# twomics_sw_led_v2.net
KiCad netlist of a schematic drawn in EAGLE
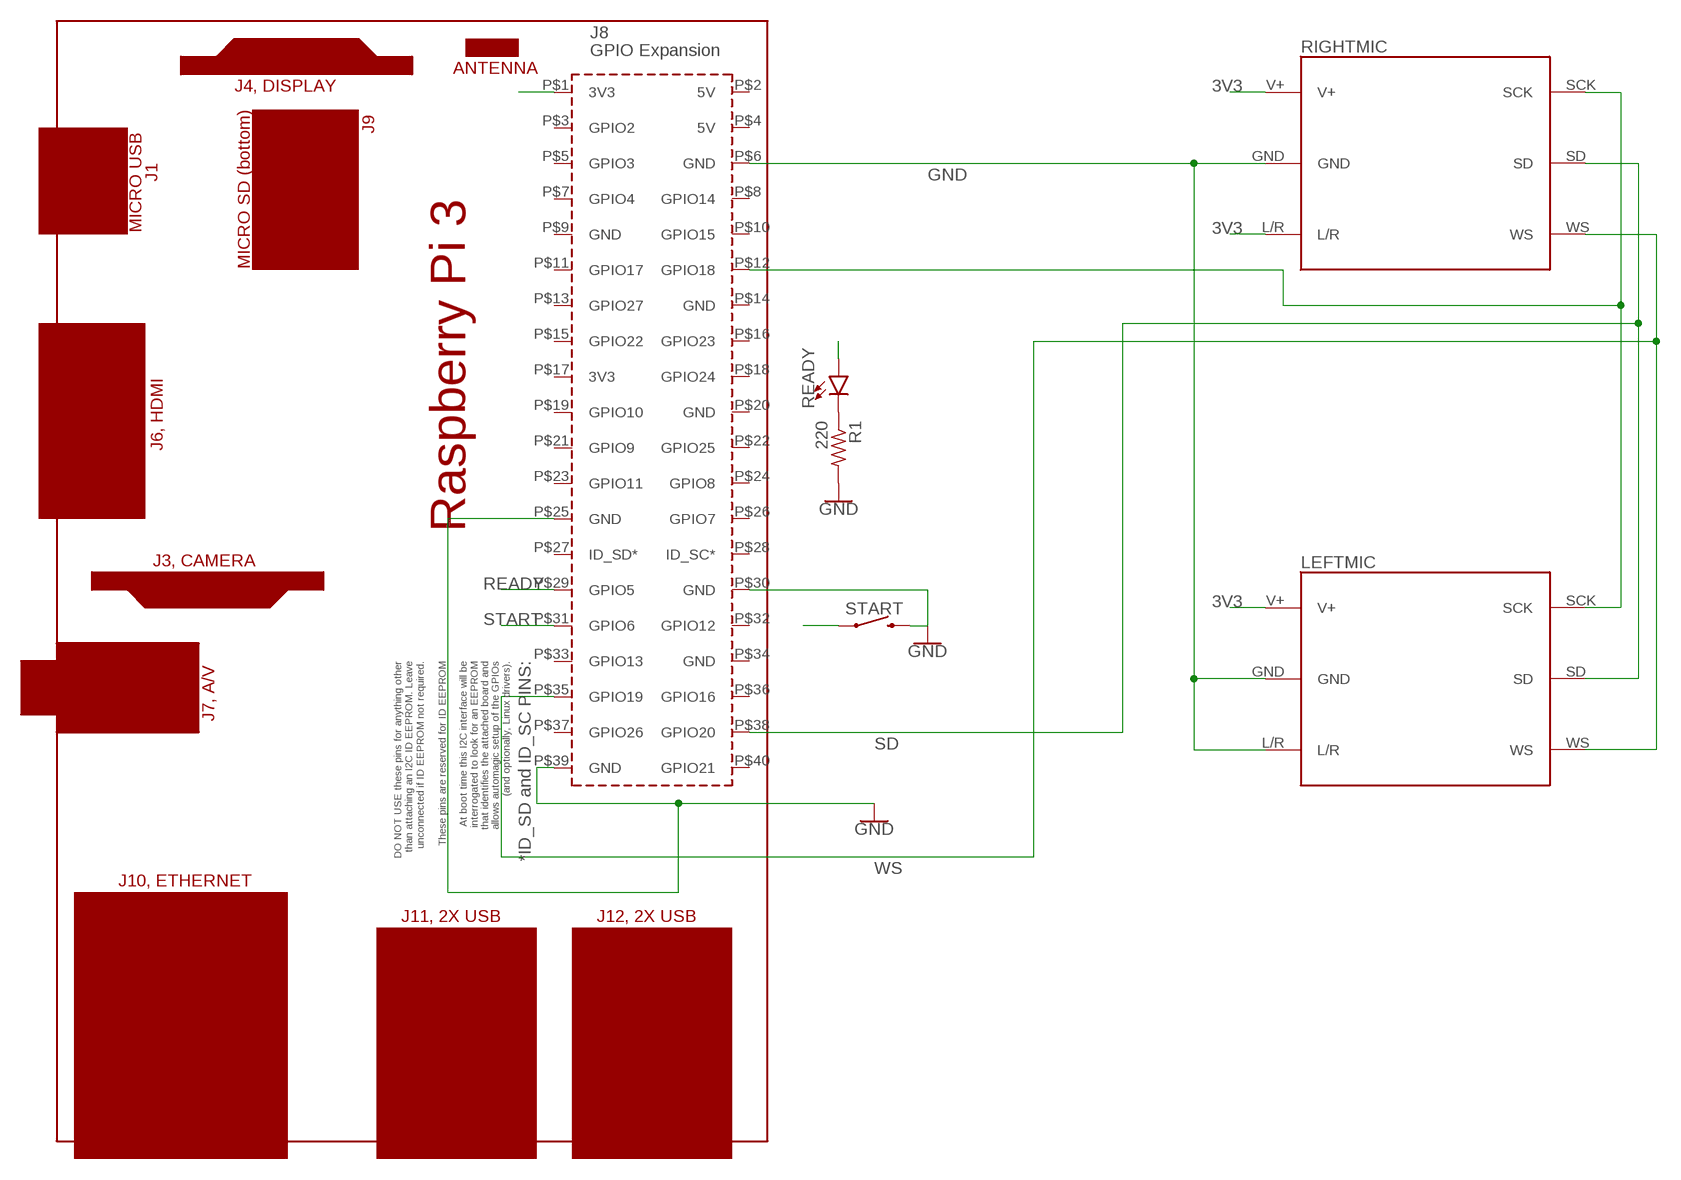
[diagram p0: schematic, sheet 1]

(export (version "E")
  (design (tool "Eeschema 10.0.6"))
  (components
    (comp (ref "LEFTMIC")
      (value "EMMIC-ICS43432")
      (footprint "eagle-import:PTH")
      (libsource (lib "eagle-import") (part "EMMIC-ICS43432"))
    )
    (comp (ref "PCB1")
      (value "RPI3_40_PIN")
      (footprint "eagle-import:40_PIN")
      (libsource (lib "eagle-import") (part "RPI3_40_PIN"))
    )
    (comp (ref "R1")
      (value "220")
      (footprint "eagle-import:0207_7")
      (libsource (lib "eagle-import") (part "R-US_0207/7"))
    )
    (comp (ref "READY")
      (value "LED3MM")
      (footprint "eagle-import:LED_3MM")
      (libsource (lib "eagle-import") (part "LED3MM"))
    )
    (comp (ref "RIGHTMIC")
      (value "EMMIC-ICS43432")
      (footprint "eagle-import:PTH")
      (libsource (lib "eagle-import") (part "EMMIC-ICS43432"))
    )
    (comp (ref "START")
      (value "MOMENTARY-SWITCH-SPST-PTH-6.0MM")
      (footprint "eagle-import:TACTILE_SWITCH_PTH_6.0MM")
      (libsource (lib "eagle-import") (part "MOMENTARY-SWITCH-SPST-PTH-6.0MM"))
    )
  )
  (nets
    (net (code "1") (name "/3V3") (class "Default")
      (node (ref "LEFTMIC") (pin "V+") (pinfunction "V+_V+") (pintype "bidirectional"))
      (node (ref "PCB1") (pin "P$1") (pinfunction "3V3_P$1") (pintype "bidirectional"))
      (node (ref "RIGHTMIC") (pin "L/R") (pinfunction "L/R_L/R") (pintype "bidirectional"))
      (node (ref "RIGHTMIC") (pin "V+") (pinfunction "V+_V+") (pintype "bidirectional"))
    )
    (net (code "2") (name "/READY") (class "Default")
      (node (ref "PCB1") (pin "P$29") (pinfunction "GPIO5_P$29") (pintype "bidirectional"))
      (node (ref "READY") (pin "A") (pinfunction "A_A") (pintype "passive"))
    )
    (net (code "3") (name "/SD") (class "Default")
      (node (ref "LEFTMIC") (pin "SD") (pinfunction "SD_SD") (pintype "bidirectional"))
      (node (ref "PCB1") (pin "P$38") (pinfunction "GPIO20_P$38") (pintype "bidirectional"))
      (node (ref "RIGHTMIC") (pin "SD") (pinfunction "SD_SD") (pintype "bidirectional"))
    )
    (net (code "4") (name "/START") (class "Default")
      (node (ref "PCB1") (pin "P$31") (pinfunction "GPIO6_P$31") (pintype "bidirectional"))
      (node (ref "START") (pin "1") (pinfunction "1_1") (pintype "passive"))
    )
    (net (code "5") (name "/WS") (class "Default")
      (node (ref "LEFTMIC") (pin "WS") (pinfunction "WS_WS") (pintype "bidirectional"))
      (node (ref "PCB1") (pin "P$35") (pinfunction "GPIO19_P$35") (pintype "bidirectional"))
      (node (ref "RIGHTMIC") (pin "WS") (pinfunction "WS_WS") (pintype "bidirectional"))
    )
    (net (code "6") (name "GND") (class "Default")
      (node (ref "LEFTMIC") (pin "GND") (pinfunction "GND_GND") (pintype "bidirectional"))
      (node (ref "LEFTMIC") (pin "L/R") (pinfunction "L/R_L/R") (pintype "bidirectional"))
      (node (ref "PCB1") (pin "P$25") (pinfunction "GND_P$25") (pintype "bidirectional"))
      (node (ref "PCB1") (pin "P$30") (pinfunction "GND_P$30") (pintype "bidirectional"))
      (node (ref "PCB1") (pin "P$39") (pinfunction "GND_P$39") (pintype "bidirectional"))
      (node (ref "PCB1") (pin "P$6") (pinfunction "GND_P$6") (pintype "bidirectional"))
      (node (ref "R1") (pin "2") (pinfunction "2_2") (pintype "passive"))
      (node (ref "RIGHTMIC") (pin "GND") (pinfunction "GND_GND") (pintype "bidirectional"))
      (node (ref "START") (pin "3") (pinfunction "2_3") (pintype "passive"))
    )
    (net (code "7") (name "Net-(PCB1-GPIO18)") (class "Default")
      (node (ref "LEFTMIC") (pin "SCK") (pinfunction "SCK_SCK") (pintype "bidirectional"))
      (node (ref "PCB1") (pin "P$12") (pinfunction "GPIO18_P$12") (pintype "bidirectional"))
      (node (ref "RIGHTMIC") (pin "SCK") (pinfunction "SCK_SCK") (pintype "bidirectional"))
    )
    (net (code "8") (name "Net-(READY-C)") (class "Default")
      (node (ref "R1") (pin "1") (pinfunction "1_1") (pintype "passive"))
      (node (ref "READY") (pin "K") (pinfunction "C_K") (pintype "passive"))
    )
    (net (code "9") (name "unconnected-(PCB1-3V3-PadP$17)") (class "Default")
      (node (ref "PCB1") (pin "P$17") (pinfunction "3V3_P$17") (pintype "bidirectional"))
    )
    (net (code "10") (name "unconnected-(PCB1-5V-PadP$2)") (class "Default")
      (node (ref "PCB1") (pin "P$2") (pinfunction "5V_P$2") (pintype "bidirectional"))
    )
    (net (code "11") (name "unconnected-(PCB1-5V-PadP$4)") (class "Default")
      (node (ref "PCB1") (pin "P$4") (pinfunction "5V_P$4") (pintype "bidirectional"))
    )
    (net (code "12") (name "unconnected-(PCB1-GND-PadP$9)") (class "Default")
      (node (ref "PCB1") (pin "P$9") (pinfunction "GND_P$9") (pintype "bidirectional"))
    )
    (net (code "13") (name "unconnected-(PCB1-GND-PadP$14)") (class "Default")
      (node (ref "PCB1") (pin "P$14") (pinfunction "GND_P$14") (pintype "bidirectional"))
    )
    (net (code "14") (name "unconnected-(PCB1-GND-PadP$20)") (class "Default")
      (node (ref "PCB1") (pin "P$20") (pinfunction "GND_P$20") (pintype "bidirectional"))
    )
    (net (code "15") (name "unconnected-(PCB1-GND-PadP$34)") (class "Default")
      (node (ref "PCB1") (pin "P$34") (pinfunction "GND_P$34") (pintype "bidirectional"))
    )
    (net (code "16") (name "unconnected-(PCB1-GPIO2-PadP$3)") (class "Default")
      (node (ref "PCB1") (pin "P$3") (pinfunction "GPIO2_P$3") (pintype "bidirectional"))
    )
    (net (code "17") (name "unconnected-(PCB1-GPIO3-PadP$5)") (class "Default")
      (node (ref "PCB1") (pin "P$5") (pinfunction "GPIO3_P$5") (pintype "bidirectional"))
    )
    (net (code "18") (name "unconnected-(PCB1-GPIO4-PadP$7)") (class "Default")
      (node (ref "PCB1") (pin "P$7") (pinfunction "GPIO4_P$7") (pintype "bidirectional"))
    )
    (net (code "19") (name "unconnected-(PCB1-GPIO7-PadP$26)") (class "Default")
      (node (ref "PCB1") (pin "P$26") (pinfunction "GPIO7_P$26") (pintype "bidirectional"))
    )
    (net (code "20") (name "unconnected-(PCB1-GPIO8-PadP$24)") (class "Default")
      (node (ref "PCB1") (pin "P$24") (pinfunction "GPIO8_P$24") (pintype "bidirectional"))
    )
    (net (code "21") (name "unconnected-(PCB1-GPIO9-PadP$21)") (class "Default")
      (node (ref "PCB1") (pin "P$21") (pinfunction "GPIO9_P$21") (pintype "bidirectional"))
    )
    (net (code "22") (name "unconnected-(PCB1-GPIO10-PadP$19)") (class "Default")
      (node (ref "PCB1") (pin "P$19") (pinfunction "GPIO10_P$19") (pintype "bidirectional"))
    )
    (net (code "23") (name "unconnected-(PCB1-GPIO11-PadP$23)") (class "Default")
      (node (ref "PCB1") (pin "P$23") (pinfunction "GPIO11_P$23") (pintype "bidirectional"))
    )
    (net (code "24") (name "unconnected-(PCB1-GPIO12-PadP$32)") (class "Default")
      (node (ref "PCB1") (pin "P$32") (pinfunction "GPIO12_P$32") (pintype "bidirectional"))
    )
    (net (code "25") (name "unconnected-(PCB1-GPIO13-PadP$33)") (class "Default")
      (node (ref "PCB1") (pin "P$33") (pinfunction "GPIO13_P$33") (pintype "bidirectional"))
    )
    (net (code "26") (name "unconnected-(PCB1-GPIO14-PadP$8)") (class "Default")
      (node (ref "PCB1") (pin "P$8") (pinfunction "GPIO14_P$8") (pintype "bidirectional"))
    )
    (net (code "27") (name "unconnected-(PCB1-GPIO15-PadP$10)") (class "Default")
      (node (ref "PCB1") (pin "P$10") (pinfunction "GPIO15_P$10") (pintype "bidirectional"))
    )
    (net (code "28") (name "unconnected-(PCB1-GPIO16-PadP$36)") (class "Default")
      (node (ref "PCB1") (pin "P$36") (pinfunction "GPIO16_P$36") (pintype "bidirectional"))
    )
    (net (code "29") (name "unconnected-(PCB1-GPIO17-PadP$11)") (class "Default")
      (node (ref "PCB1") (pin "P$11") (pinfunction "GPIO17_P$11") (pintype "bidirectional"))
    )
    (net (code "30") (name "unconnected-(PCB1-GPIO21-PadP$40)") (class "Default")
      (node (ref "PCB1") (pin "P$40") (pinfunction "GPIO21_P$40") (pintype "bidirectional"))
    )
    (net (code "31") (name "unconnected-(PCB1-GPIO22-PadP$15)") (class "Default")
      (node (ref "PCB1") (pin "P$15") (pinfunction "GPIO22_P$15") (pintype "bidirectional"))
    )
    (net (code "32") (name "unconnected-(PCB1-GPIO23-PadP$16)") (class "Default")
      (node (ref "PCB1") (pin "P$16") (pinfunction "GPIO23_P$16") (pintype "bidirectional"))
    )
    (net (code "33") (name "unconnected-(PCB1-GPIO24-PadP$18)") (class "Default")
      (node (ref "PCB1") (pin "P$18") (pinfunction "GPIO24_P$18") (pintype "bidirectional"))
    )
    (net (code "34") (name "unconnected-(PCB1-GPIO25-PadP$22)") (class "Default")
      (node (ref "PCB1") (pin "P$22") (pinfunction "GPIO25_P$22") (pintype "bidirectional"))
    )
    (net (code "35") (name "unconnected-(PCB1-GPIO26-PadP$37)") (class "Default")
      (node (ref "PCB1") (pin "P$37") (pinfunction "GPIO26_P$37") (pintype "bidirectional"))
    )
    (net (code "36") (name "unconnected-(PCB1-GPIO27-PadP$13)") (class "Default")
      (node (ref "PCB1") (pin "P$13") (pinfunction "GPIO27_P$13") (pintype "bidirectional"))
    )
    (net (code "37") (name "unconnected-(PCB1-ID_SC*-PadP$28)") (class "Default")
      (node (ref "PCB1") (pin "P$28") (pinfunction "ID_SC*_P$28") (pintype "bidirectional"))
    )
    (net (code "38") (name "unconnected-(PCB1-ID_SD*-PadP$27)") (class "Default")
      (node (ref "PCB1") (pin "P$27") (pinfunction "ID_SD*_P$27") (pintype "bidirectional"))
    )
  )
)
